# T14_SuperDuperRev4V01.net
KiCad netlist of a schematic drawn in EAGLE
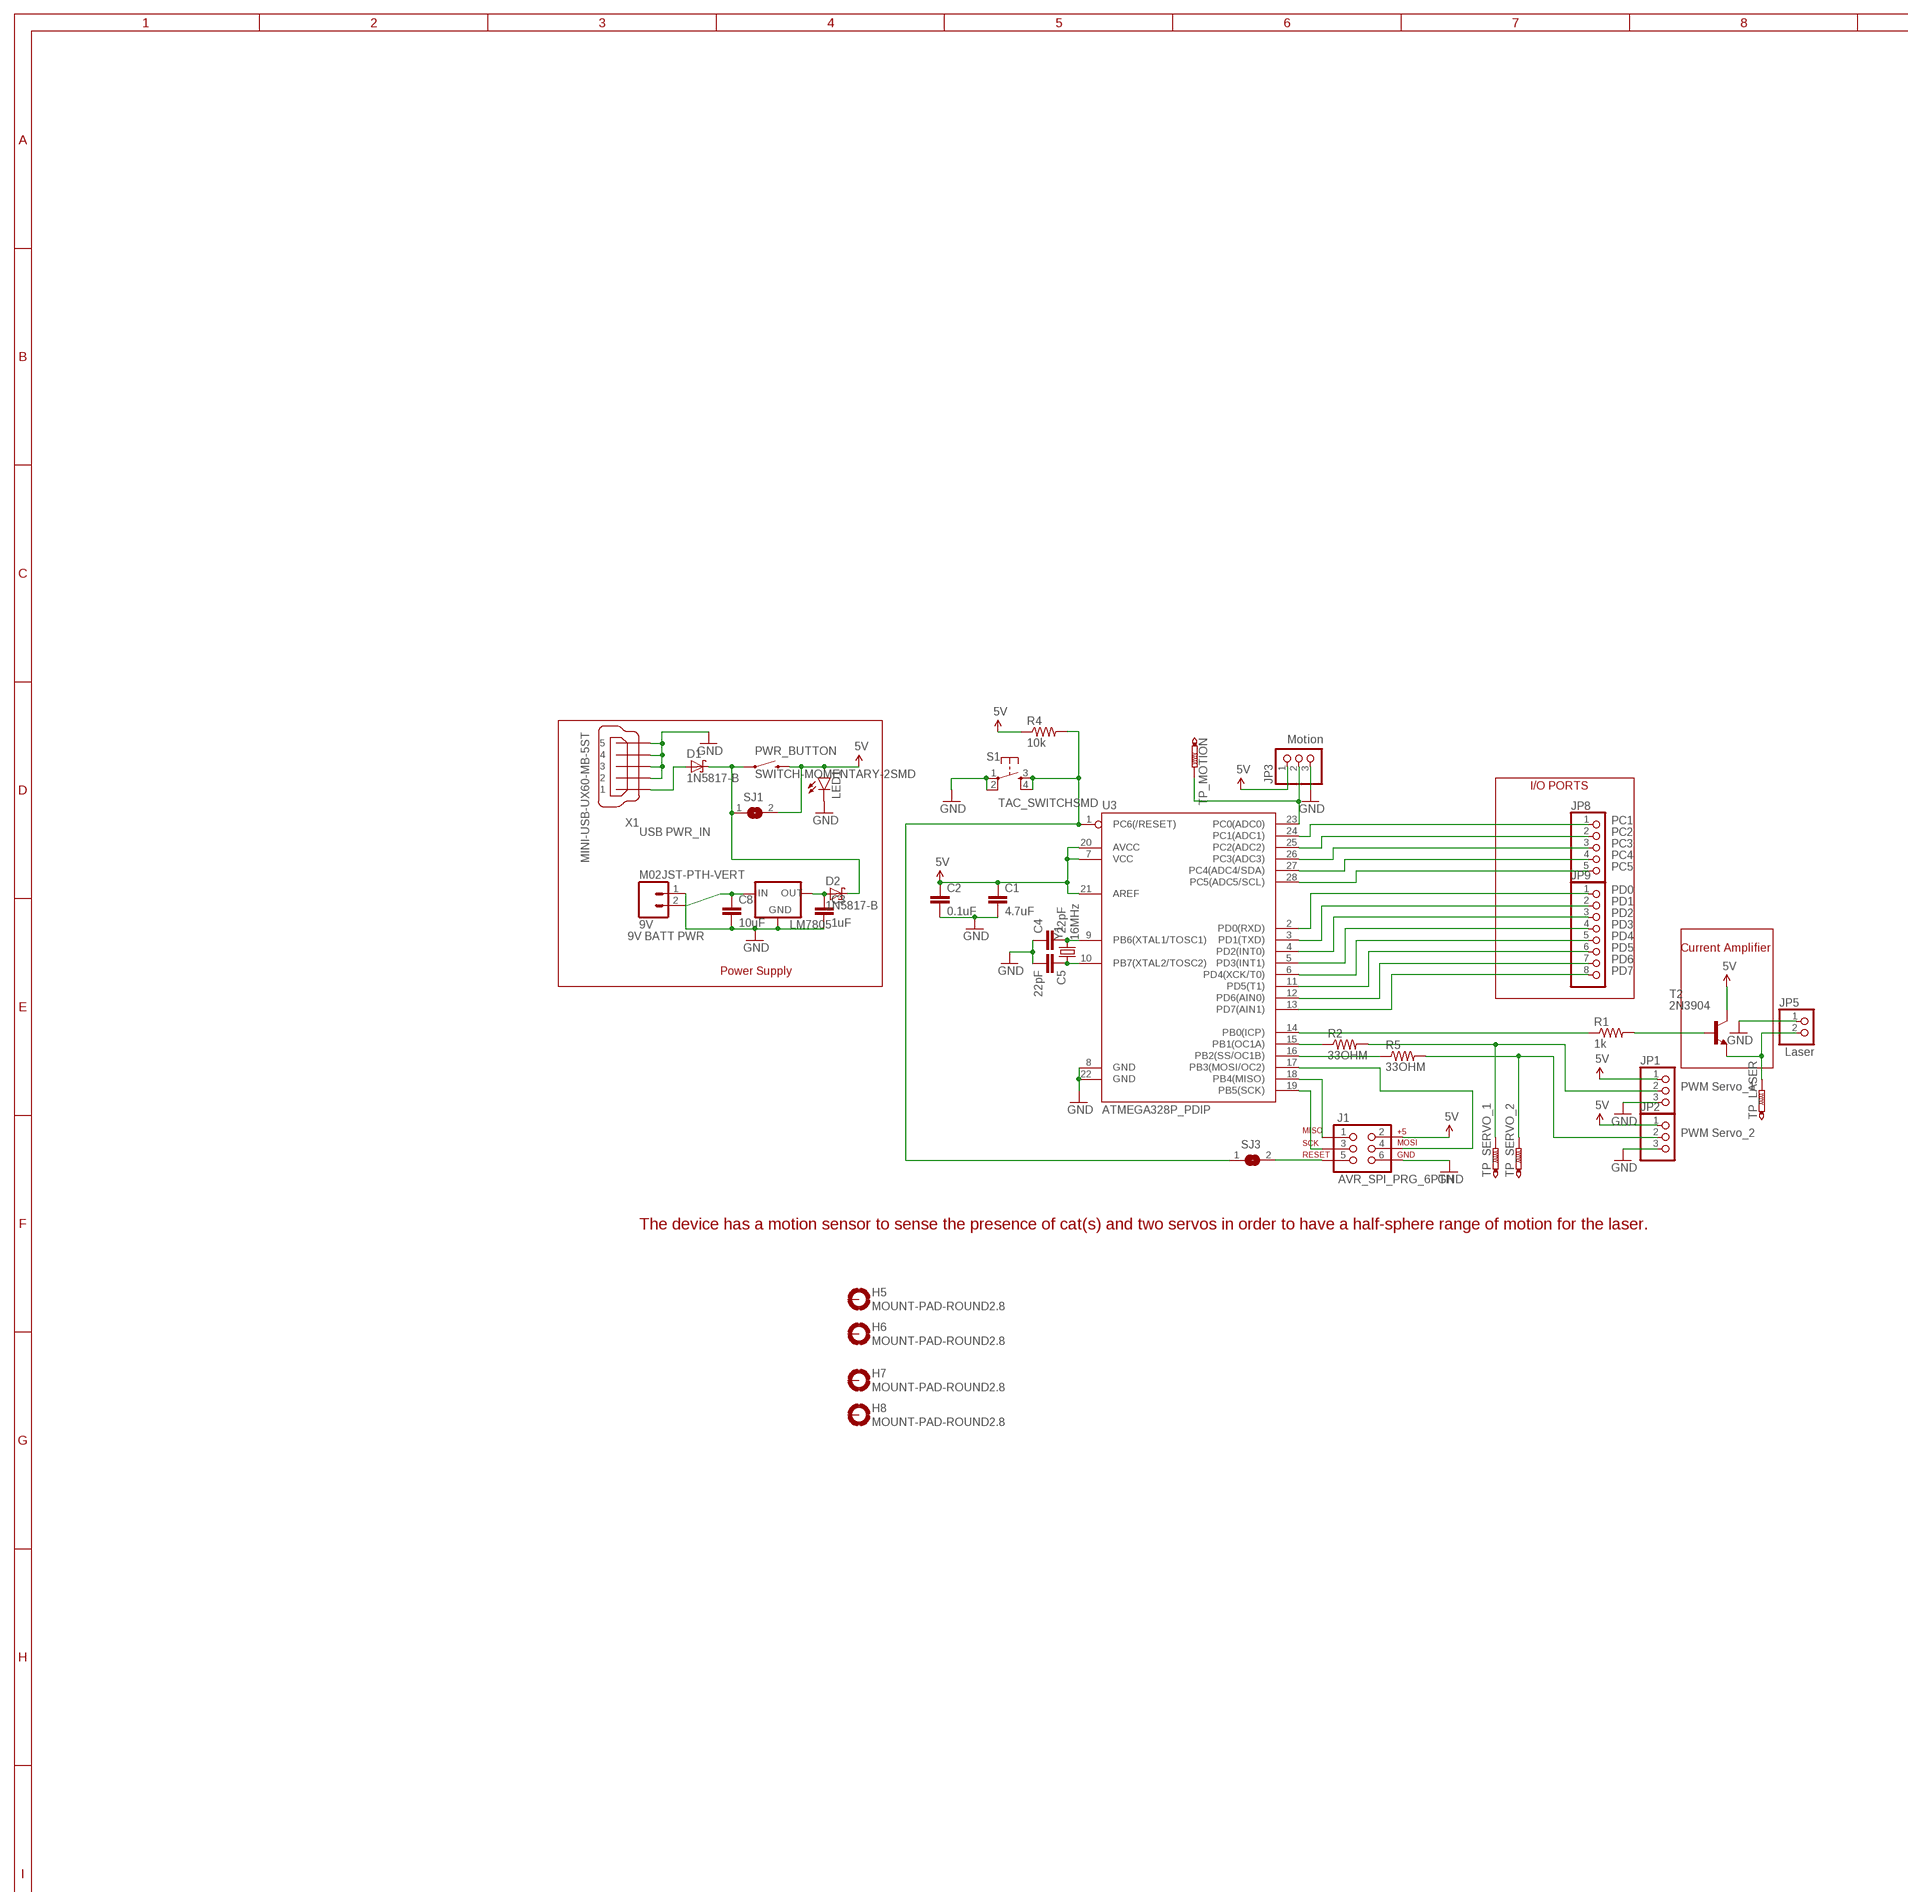
[diagram p0: schematic, sheet 1, part 1 of 2]
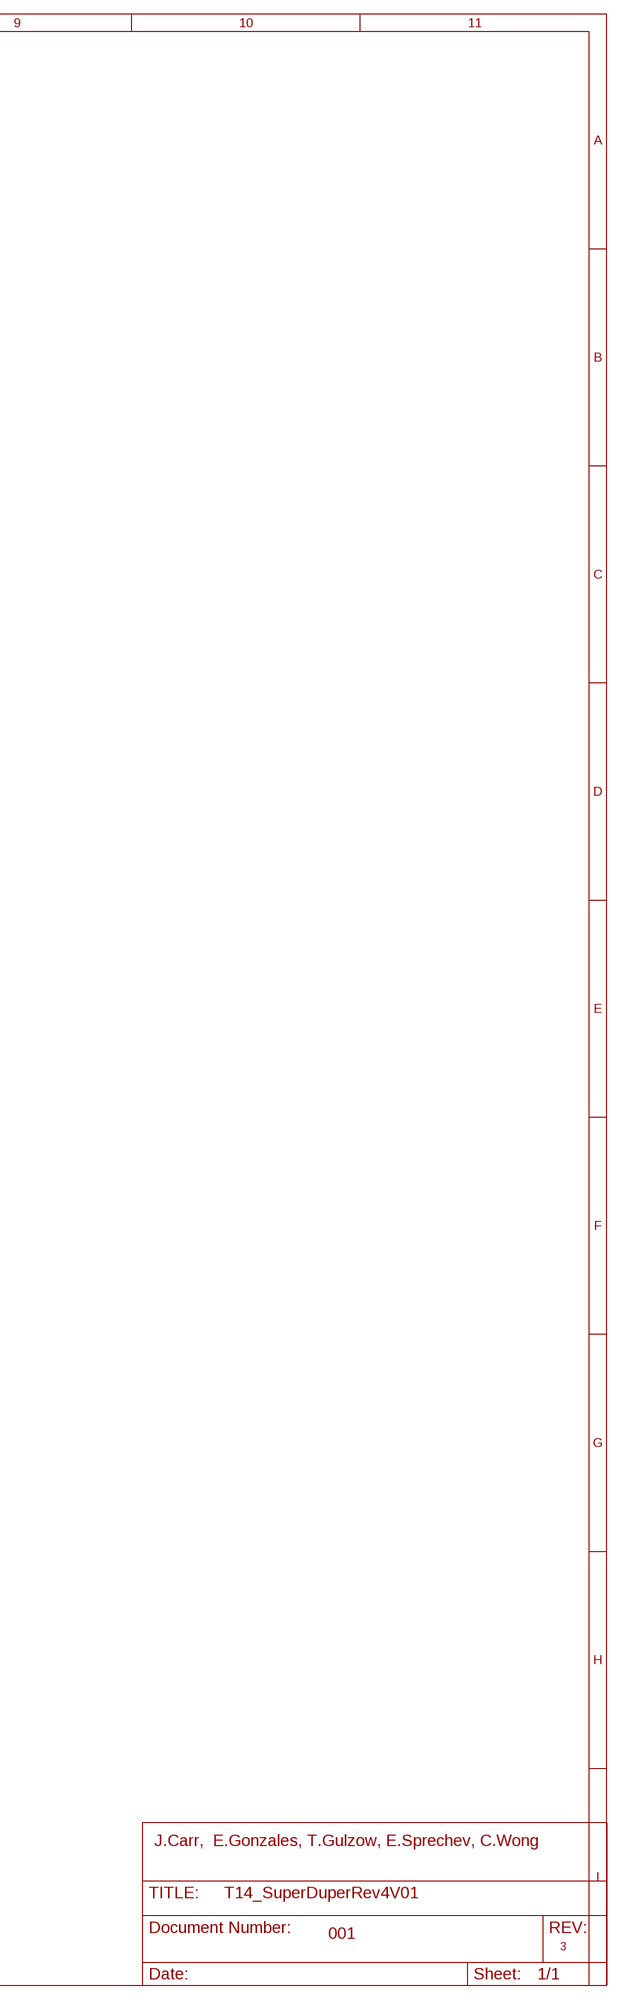
[diagram p1: schematic, sheet 1, part 2 of 2]

(export (version "E")
  (design (tool "Eeschema 10.0.6"))
  (components
    (comp (ref "9V")
      (value "M02JST-PTH-VERT")
      (footprint "eagle-import:JST-2-PTH-VERT")
      (libsource (lib "eagle-import") (part "M02JST-PTH-VERT"))
    )
    (comp (ref "C1")
      (value "4.7uF")
      (footprint "eagle-import:0603-CAP")
      (libsource (lib "eagle-import") (part "4.7UF-6.3V-10%(0603)0603"))
    )
    (comp (ref "C2")
      (value "0.1uF")
      (footprint "eagle-import:0603-CAP")
      (libsource (lib "eagle-import") (part "0.1UF-25V(+80/-20%)(0603)"))
    )
    (comp (ref "C3")
      (value "1uF")
      (footprint "eagle-import:0603-CAP")
      (fields (field (name "PROD_ID") "CAP-00810"))
      (libsource (lib "eagle-import") (part "0.1UF-25V(+80/-20%)(0603)"))
    )
    (comp (ref "C4")
      (value "22pF")
      (footprint "eagle-import:0603-CAP")
      (libsource (lib "eagle-import") (part "4.7UF-6.3V-10%(0603)0603"))
    )
    (comp (ref "C5")
      (value "22pF")
      (footprint "eagle-import:0603-CAP")
      (libsource (lib "eagle-import") (part "4.7UF-6.3V-10%(0603)0603"))
    )
    (comp (ref "C8")
      (value "10uF")
      (footprint "eagle-import:0603-CAP")
      (fields (field (name "PROD_ID") "CAP-00810"))
      (libsource (lib "eagle-import") (part "0.1UF-25V(+80/-20%)(0603)"))
    )
    (comp (ref "D1")
      (value "1N5817-B")
      (footprint "eagle-import:DO41-7.6")
      (libsource (lib "eagle-import") (part "1N5817-B"))
    )
    (comp (ref "D2")
      (value "1N5817-B")
      (footprint "eagle-import:DO41-7.6")
      (libsource (lib "eagle-import") (part "1N5817-B"))
    )
    (comp (ref "H5")
      (value "MOUNT-PAD-ROUND2.8")
      (footprint "eagle-import:2,8-PAD")
      (libsource (lib "eagle-import") (part "MOUNT-PAD-ROUND2.8"))
    )
    (comp (ref "H6")
      (value "MOUNT-PAD-ROUND2.8")
      (footprint "eagle-import:2,8-PAD")
      (libsource (lib "eagle-import") (part "MOUNT-PAD-ROUND2.8"))
    )
    (comp (ref "H7")
      (value "MOUNT-PAD-ROUND2.8")
      (footprint "eagle-import:2,8-PAD")
      (libsource (lib "eagle-import") (part "MOUNT-PAD-ROUND2.8"))
    )
    (comp (ref "H8")
      (value "MOUNT-PAD-ROUND2.8")
      (footprint "eagle-import:2,8-PAD")
      (libsource (lib "eagle-import") (part "MOUNT-PAD-ROUND2.8"))
    )
    (comp (ref "J1")
      (value "AVR_SPI_PRG_6PTH")
      (footprint "eagle-import:2X3")
      (libsource (lib "eagle-import") (part "AVR_SPI_PRG_6PTH"))
    )
    (comp (ref "JP1")
      (value "PINHD-1X3")
      (footprint "eagle-import:1X03")
      (libsource (lib "eagle-import") (part "PINHD-1X3"))
    )
    (comp (ref "JP2")
      (value "PINHD-1X3")
      (footprint "eagle-import:1X03")
      (libsource (lib "eagle-import") (part "PINHD-1X3"))
    )
    (comp (ref "JP3")
      (value "PINHD-1X3")
      (footprint "eagle-import:1X03")
      (libsource (lib "eagle-import") (part "PINHD-1X3"))
    )
    (comp (ref "JP5")
      (value "PINHD-1X2")
      (footprint "eagle-import:1X02")
      (libsource (lib "eagle-import") (part "PINHD-1X2"))
    )
    (comp (ref "JP8")
      (value "PINHD-1X5")
      (footprint "eagle-import:1X05")
      (libsource (lib "eagle-import") (part "PINHD-1X5"))
    )
    (comp (ref "JP9")
      (value "PINHD-1X8")
      (footprint "eagle-import:1X08")
      (libsource (lib "eagle-import") (part "PINHD-1X8"))
    )
    (comp (ref "LED1")
      (value "LED-3MM-NO_SILK")
      (footprint "eagle-import:LED3MM-NS")
      (libsource (lib "eagle-import") (part "LED-3MM-NO_SILK"))
    )
    (comp (ref "LM7805")
      (value "V_REG_78XXSIDE")
      (footprint "eagle-import:78XXL")
      (libsource (lib "eagle-import") (part "V_REG_78XXSIDE"))
    )
    (comp (ref "PWR_BUTTON")
      (value "SWITCH-MOMENTARY-2SMD")
      (footprint "eagle-import:TACTILE-SWITCH-SMD")
      (libsource (lib "eagle-import") (part "SWITCH-MOMENTARY-2SMD"))
    )
    (comp (ref "R1")
      (value "1k")
      (footprint "eagle-import:0603")
      (libsource (lib "eagle-import") (part "33OHM1/10W1%(0603)"))
    )
    (comp (ref "R2")
      (value "33OHM")
      (footprint "eagle-import:0603")
      (libsource (lib "eagle-import") (part "33OHM1/10W1%(0603)"))
    )
    (comp (ref "R4")
      (value "10k")
      (footprint "eagle-import:0603")
      (libsource (lib "eagle-import") (part "33OHM1/10W1%(0603)"))
    )
    (comp (ref "R5")
      (value "33OHM")
      (footprint "eagle-import:0603")
      (libsource (lib "eagle-import") (part "33OHM1/10W1%(0603)"))
    )
    (comp (ref "S1")
      (value "TAC_SWITCHSMD")
      (footprint "eagle-import:TACTILE-SWITCH-SMD")
      (libsource (lib "eagle-import") (part "TAC_SWITCHSMD"))
    )
    (comp (ref "SJ1") (value "SJ") (footprint "eagle-import:SJ") (libsource (lib "eagle-import") (part "SJ")))
    (comp (ref "SJ3") (value "SJ") (footprint "eagle-import:SJ") (libsource (lib "eagle-import") (part "SJ")))
    (comp (ref "T2")
      (value "2N3904")
      (footprint "eagle-import:TO92")
      (libsource (lib "eagle-import") (part "2N3904"))
    )
    (comp (ref "TP_LASER")
      (value "PTR1B2,54")
      (footprint "eagle-import:B2,54")
      (libsource (lib "eagle-import") (part "PTR1B2,54"))
    )
    (comp (ref "TP_MOTION")
      (value "PTR1B2,54")
      (footprint "eagle-import:B2,54")
      (libsource (lib "eagle-import") (part "PTR1B2,54"))
    )
    (comp (ref "TP_SERVO_1")
      (value "PTR1B2,54")
      (footprint "eagle-import:B2,54")
      (libsource (lib "eagle-import") (part "PTR1B2,54"))
    )
    (comp (ref "TP_SERVO_2")
      (value "PTR1B2,54")
      (footprint "eagle-import:B2,54")
      (libsource (lib "eagle-import") (part "PTR1B2,54"))
    )
    (comp (ref "U3")
      (value "ATMEGA328P_PDIP")
      (footprint "eagle-import:DIL28-3")
      (libsource (lib "eagle-import") (part "ATMEGA328P_PDIP"))
    )
    (comp (ref "X1")
      (value "MINI-USB-UX60-MB-5ST")
      (footprint "eagle-import:UX60-MB-5ST")
      (libsource (lib "eagle-import") (part "MINI-USB-UX60-MB-5ST"))
    )
    (comp (ref "Y1")
      (value "16MHz")
      (footprint "eagle-import:CRYSTAL-SMD-10.5X4.8-2PIN")
      (libsource (lib "eagle-import") (part "CRYSTAL10.5X4.8"))
    )
  )
  (nets
    (net (code "1") (name "5V") (class "Default")
      (node (ref "C1") (pin "1") (pinfunction "1_1") (pintype "passive"))
      (node (ref "C2") (pin "1") (pinfunction "1_1") (pintype "passive"))
      (node (ref "J1") (pin "2") (pinfunction "2_2") (pintype "passive"))
      (node (ref "JP1") (pin "1") (pinfunction "1_1") (pintype "passive"))
      (node (ref "JP2") (pin "1") (pinfunction "1_1") (pintype "passive"))
      (node (ref "JP3") (pin "1") (pinfunction "1_1") (pintype "passive"))
      (node (ref "LED1") (pin "A") (pinfunction "A_A") (pintype "passive"))
      (node (ref "PWR_BUTTON") (pin "3") (pinfunction "2_3") (pintype "passive"))
      (node (ref "R4") (pin "1") (pinfunction "1_1") (pintype "passive"))
      (node (ref "SJ1") (pin "2") (pinfunction "2_2") (pintype "passive"))
      (node (ref "T2") (pin "1") (pinfunction "C_1") (pintype "passive"))
      (node (ref "U3") (pin "20") (pinfunction "AVCC_20") (pintype "bidirectional"))
      (node (ref "U3") (pin "21") (pinfunction "AREF_21") (pintype "bidirectional"))
      (node (ref "U3") (pin "7") (pinfunction "VCC_7") (pintype "bidirectional"))
    )
    (net (code "2") (name "GND") (class "Default")
      (node (ref "9V") (pin "1") (pinfunction "1_1") (pintype "passive"))
      (node (ref "C1") (pin "2") (pinfunction "2_2") (pintype "passive"))
      (node (ref "C2") (pin "2") (pinfunction "2_2") (pintype "passive"))
      (node (ref "C3") (pin "2") (pinfunction "2_2") (pintype "passive"))
      (node (ref "C4") (pin "1") (pinfunction "1_1") (pintype "passive"))
      (node (ref "C5") (pin "2") (pinfunction "2_2") (pintype "passive"))
      (node (ref "C8") (pin "2") (pinfunction "2_2") (pintype "passive"))
      (node (ref "J1") (pin "6") (pinfunction "6_6") (pintype "passive"))
      (node (ref "JP1") (pin "3") (pinfunction "3_3") (pintype "passive"))
      (node (ref "JP2") (pin "3") (pinfunction "3_3") (pintype "passive"))
      (node (ref "JP3") (pin "3") (pinfunction "3_3") (pintype "passive"))
      (node (ref "JP5") (pin "1") (pinfunction "1_1") (pintype "passive"))
      (node (ref "LED1") (pin "K") (pinfunction "C_K") (pintype "passive"))
      (node (ref "LM7805") (pin "GND") (pinfunction "GND_GND") (pintype "input"))
      (node (ref "S1") (pin "1") (pinfunction "1_1") (pintype "passive"))
      (node (ref "S1") (pin "2") (pinfunction "2_2") (pintype "passive"))
      (node (ref "U3") (pin "22") (pinfunction "GND_22") (pintype "bidirectional"))
      (node (ref "U3") (pin "8") (pinfunction "GND_8") (pintype "bidirectional"))
      (node (ref "X1") (pin "2") (pinfunction "2_2") (pintype "input"))
      (node (ref "X1") (pin "3") (pinfunction "3_3") (pintype "input"))
      (node (ref "X1") (pin "4") (pinfunction "4_4") (pintype "input"))
      (node (ref "X1") (pin "5") (pinfunction "5_5") (pintype "input"))
    )
    (net (code "3") (name "Net-(9V-Pad2)") (class "Default")
      (node (ref "9V") (pin "2") (pinfunction "2_2") (pintype "passive"))
      (node (ref "C8") (pin "1") (pinfunction "1_1") (pintype "passive"))
      (node (ref "LM7805") (pin "IN") (pinfunction "IN_IN") (pintype "input"))
    )
    (net (code "4") (name "Net-(C3-Pad1)") (class "Default")
      (node (ref "C3") (pin "1") (pinfunction "1_1") (pintype "passive"))
      (node (ref "D2") (pin "A") (pinfunction "A_A") (pintype "passive"))
      (node (ref "LM7805") (pin "OUT") (pinfunction "OUT_OUT") (pintype "output"))
    )
    (net (code "5") (name "Net-(D1-PadA)") (class "Default")
      (node (ref "D1") (pin "A") (pinfunction "A_A") (pintype "passive"))
      (node (ref "X1") (pin "1") (pinfunction "1_1") (pintype "input"))
    )
    (net (code "6") (name "Net-(D1-PadC)") (class "Default")
      (node (ref "D1") (pin "C") (pinfunction "C_C") (pintype "passive"))
      (node (ref "D2") (pin "C") (pinfunction "C_C") (pintype "passive"))
      (node (ref "PWR_BUTTON") (pin "1") (pinfunction "1_1") (pintype "passive"))
      (node (ref "SJ1") (pin "1") (pinfunction "1_1") (pintype "passive"))
    )
    (net (code "7") (name "Net-(J1-Pad5)") (class "Default")
      (node (ref "J1") (pin "5") (pinfunction "5_5") (pintype "passive"))
      (node (ref "SJ3") (pin "2") (pinfunction "2_2") (pintype "passive"))
    )
    (net (code "8") (name "Net-(JP1-Pad2)") (class "Default")
      (node (ref "JP1") (pin "2") (pinfunction "2_2") (pintype "passive"))
      (node (ref "R2") (pin "2") (pinfunction "2_2") (pintype "passive"))
      (node (ref "TP_SERVO_1") (pin "TP") (pinfunction "TP_TP") (pintype "input"))
    )
    (net (code "9") (name "Net-(JP2-Pad2)") (class "Default")
      (node (ref "JP2") (pin "2") (pinfunction "2_2") (pintype "passive"))
      (node (ref "R5") (pin "2") (pinfunction "2_2") (pintype "passive"))
      (node (ref "TP_SERVO_2") (pin "TP") (pinfunction "TP_TP") (pintype "input"))
    )
    (net (code "10") (name "Net-(T2-B)") (class "Default")
      (node (ref "R1") (pin "2") (pinfunction "2_2") (pintype "passive"))
      (node (ref "T2") (pin "2") (pinfunction "B_2") (pintype "passive"))
    )
    (net (code "11") (name "Net-(T2-E)") (class "Default")
      (node (ref "JP5") (pin "2") (pinfunction "2_2") (pintype "passive"))
      (node (ref "T2") (pin "3") (pinfunction "E_3") (pintype "passive"))
      (node (ref "TP_LASER") (pin "TP") (pinfunction "TP_TP") (pintype "input"))
    )
    (net (code "12") (name "Net-(U3-PB0(ICP))") (class "Default")
      (node (ref "R1") (pin "1") (pinfunction "1_1") (pintype "passive"))
      (node (ref "U3") (pin "14") (pinfunction "PB0(ICP)_14") (pintype "bidirectional"))
    )
    (net (code "13") (name "Net-(U3-PB1(OC1A))") (class "Default")
      (node (ref "R2") (pin "1") (pinfunction "1_1") (pintype "passive"))
      (node (ref "U3") (pin "15") (pinfunction "PB1(OC1A)_15") (pintype "bidirectional"))
    )
    (net (code "14") (name "Net-(U3-PB2(SS{slash}OC1B))") (class "Default")
      (node (ref "R5") (pin "1") (pinfunction "1_1") (pintype "passive"))
      (node (ref "U3") (pin "16") (pinfunction "PB2(SS/OC1B)_16") (pintype "bidirectional"))
    )
    (net (code "15") (name "Net-(U3-PB3(MOSI{slash}OC2))") (class "Default")
      (node (ref "J1") (pin "4") (pinfunction "4_4") (pintype "passive"))
      (node (ref "U3") (pin "17") (pinfunction "PB3(MOSI/OC2)_17") (pintype "bidirectional"))
    )
    (net (code "16") (name "Net-(U3-PB4(MISO))") (class "Default")
      (node (ref "J1") (pin "1") (pinfunction "1_1") (pintype "passive"))
      (node (ref "U3") (pin "18") (pinfunction "PB4(MISO)_18") (pintype "bidirectional"))
    )
    (net (code "17") (name "Net-(U3-PB5(SCK))") (class "Default")
      (node (ref "J1") (pin "3") (pinfunction "3_3") (pintype "passive"))
      (node (ref "U3") (pin "19") (pinfunction "PB5(SCK)_19") (pintype "bidirectional"))
    )
    (net (code "18") (name "Net-(U3-PB6(XTAL1{slash}TOSC1))") (class "Default")
      (node (ref "C4") (pin "2") (pinfunction "2_2") (pintype "passive"))
      (node (ref "U3") (pin "9") (pinfunction "PB6(XTAL1/TOSC1)_9") (pintype "bidirectional"))
      (node (ref "Y1") (pin "P$2") (pinfunction "2_P$2") (pintype "passive"))
    )
    (net (code "19") (name "Net-(U3-PB7(XTAL2{slash}TOSC2))") (class "Default")
      (node (ref "C5") (pin "1") (pinfunction "1_1") (pintype "passive"))
      (node (ref "U3") (pin "10") (pinfunction "PB7(XTAL2/TOSC2)_10") (pintype "bidirectional"))
      (node (ref "Y1") (pin "P$1") (pinfunction "1_P$1") (pintype "passive"))
    )
    (net (code "20") (name "Net-(U3-PC0(ADC0))") (class "Default")
      (node (ref "JP3") (pin "2") (pinfunction "2_2") (pintype "passive"))
      (node (ref "TP_MOTION") (pin "TP") (pinfunction "TP_TP") (pintype "input"))
      (node (ref "U3") (pin "23") (pinfunction "PC0(ADC0)_23") (pintype "bidirectional"))
    )
    (net (code "21") (name "Net-(U3-PC1(ADC1))") (class "Default")
      (node (ref "JP8") (pin "1") (pinfunction "1_1") (pintype "passive"))
      (node (ref "U3") (pin "24") (pinfunction "PC1(ADC1)_24") (pintype "bidirectional"))
    )
    (net (code "22") (name "Net-(U3-PC2(ADC2))") (class "Default")
      (node (ref "JP8") (pin "2") (pinfunction "2_2") (pintype "passive"))
      (node (ref "U3") (pin "25") (pinfunction "PC2(ADC2)_25") (pintype "bidirectional"))
    )
    (net (code "23") (name "Net-(U3-PC3(ADC3))") (class "Default")
      (node (ref "JP8") (pin "3") (pinfunction "3_3") (pintype "passive"))
      (node (ref "U3") (pin "26") (pinfunction "PC3(ADC3)_26") (pintype "bidirectional"))
    )
    (net (code "24") (name "Net-(U3-PC4(ADC4{slash}SDA))") (class "Default")
      (node (ref "JP8") (pin "4") (pinfunction "4_4") (pintype "passive"))
      (node (ref "U3") (pin "27") (pinfunction "PC4(ADC4/SDA)_27") (pintype "bidirectional"))
    )
    (net (code "25") (name "Net-(U3-PC5(ADC5{slash}SCL))") (class "Default")
      (node (ref "JP8") (pin "5") (pinfunction "5_5") (pintype "passive"))
      (node (ref "U3") (pin "28") (pinfunction "PC5(ADC5/SCL)_28") (pintype "bidirectional"))
    )
    (net (code "26") (name "Net-(U3-PC6({slash}RESET))") (class "Default")
      (node (ref "R4") (pin "2") (pinfunction "2_2") (pintype "passive"))
      (node (ref "S1") (pin "3") (pinfunction "3_3") (pintype "passive"))
      (node (ref "S1") (pin "4") (pinfunction "4_4") (pintype "passive"))
      (node (ref "SJ3") (pin "1") (pinfunction "1_1") (pintype "passive"))
      (node (ref "U3") (pin "1") (pinfunction "PC6(/RESET)_1") (pintype "bidirectional"))
    )
    (net (code "27") (name "Net-(U3-PD0(RXD))") (class "Default")
      (node (ref "JP9") (pin "1") (pinfunction "1_1") (pintype "passive"))
      (node (ref "U3") (pin "2") (pinfunction "PD0(RXD)_2") (pintype "bidirectional"))
    )
    (net (code "28") (name "Net-(U3-PD1(TXD))") (class "Default")
      (node (ref "JP9") (pin "2") (pinfunction "2_2") (pintype "passive"))
      (node (ref "U3") (pin "3") (pinfunction "PD1(TXD)_3") (pintype "bidirectional"))
    )
    (net (code "29") (name "Net-(U3-PD2(INT0))") (class "Default")
      (node (ref "JP9") (pin "3") (pinfunction "3_3") (pintype "passive"))
      (node (ref "U3") (pin "4") (pinfunction "PD2(INT0)_4") (pintype "bidirectional"))
    )
    (net (code "30") (name "Net-(U3-PD3(INT1))") (class "Default")
      (node (ref "JP9") (pin "4") (pinfunction "4_4") (pintype "passive"))
      (node (ref "U3") (pin "5") (pinfunction "PD3(INT1)_5") (pintype "bidirectional"))
    )
    (net (code "31") (name "Net-(U3-PD4(XCK{slash}T0))") (class "Default")
      (node (ref "JP9") (pin "5") (pinfunction "5_5") (pintype "passive"))
      (node (ref "U3") (pin "6") (pinfunction "PD4(XCK/T0)_6") (pintype "bidirectional"))
    )
    (net (code "32") (name "Net-(U3-PD5(T1))") (class "Default")
      (node (ref "JP9") (pin "6") (pinfunction "6_6") (pintype "passive"))
      (node (ref "U3") (pin "11") (pinfunction "PD5(T1)_11") (pintype "bidirectional"))
    )
    (net (code "33") (name "Net-(U3-PD6(AIN0))") (class "Default")
      (node (ref "JP9") (pin "7") (pinfunction "7_7") (pintype "passive"))
      (node (ref "U3") (pin "12") (pinfunction "PD6(AIN0)_12") (pintype "bidirectional"))
    )
    (net (code "34") (name "Net-(U3-PD7(AIN1))") (class "Default")
      (node (ref "JP9") (pin "8") (pinfunction "8_8") (pintype "passive"))
      (node (ref "U3") (pin "13") (pinfunction "PD7(AIN1)_13") (pintype "bidirectional"))
    )
    (net (code "35") (name "unconnected-(H5-MOUNT-PadB2,8)") (class "Default")
      (node (ref "H5") (pin "B2,8") (pinfunction "MOUNT_B2,8") (pintype "passive"))
    )
    (net (code "36") (name "unconnected-(H6-MOUNT-PadB2,8)") (class "Default")
      (node (ref "H6") (pin "B2,8") (pinfunction "MOUNT_B2,8") (pintype "passive"))
    )
    (net (code "37") (name "unconnected-(H7-MOUNT-PadB2,8)") (class "Default")
      (node (ref "H7") (pin "B2,8") (pinfunction "MOUNT_B2,8") (pintype "passive"))
    )
    (net (code "38") (name "unconnected-(H8-MOUNT-PadB2,8)") (class "Default")
      (node (ref "H8") (pin "B2,8") (pinfunction "MOUNT_B2,8") (pintype "passive"))
    )
  )
)
